# USBINFRTransiever_Microcontroller.net
KiCad netlist of a schematic drawn in Altium Designer
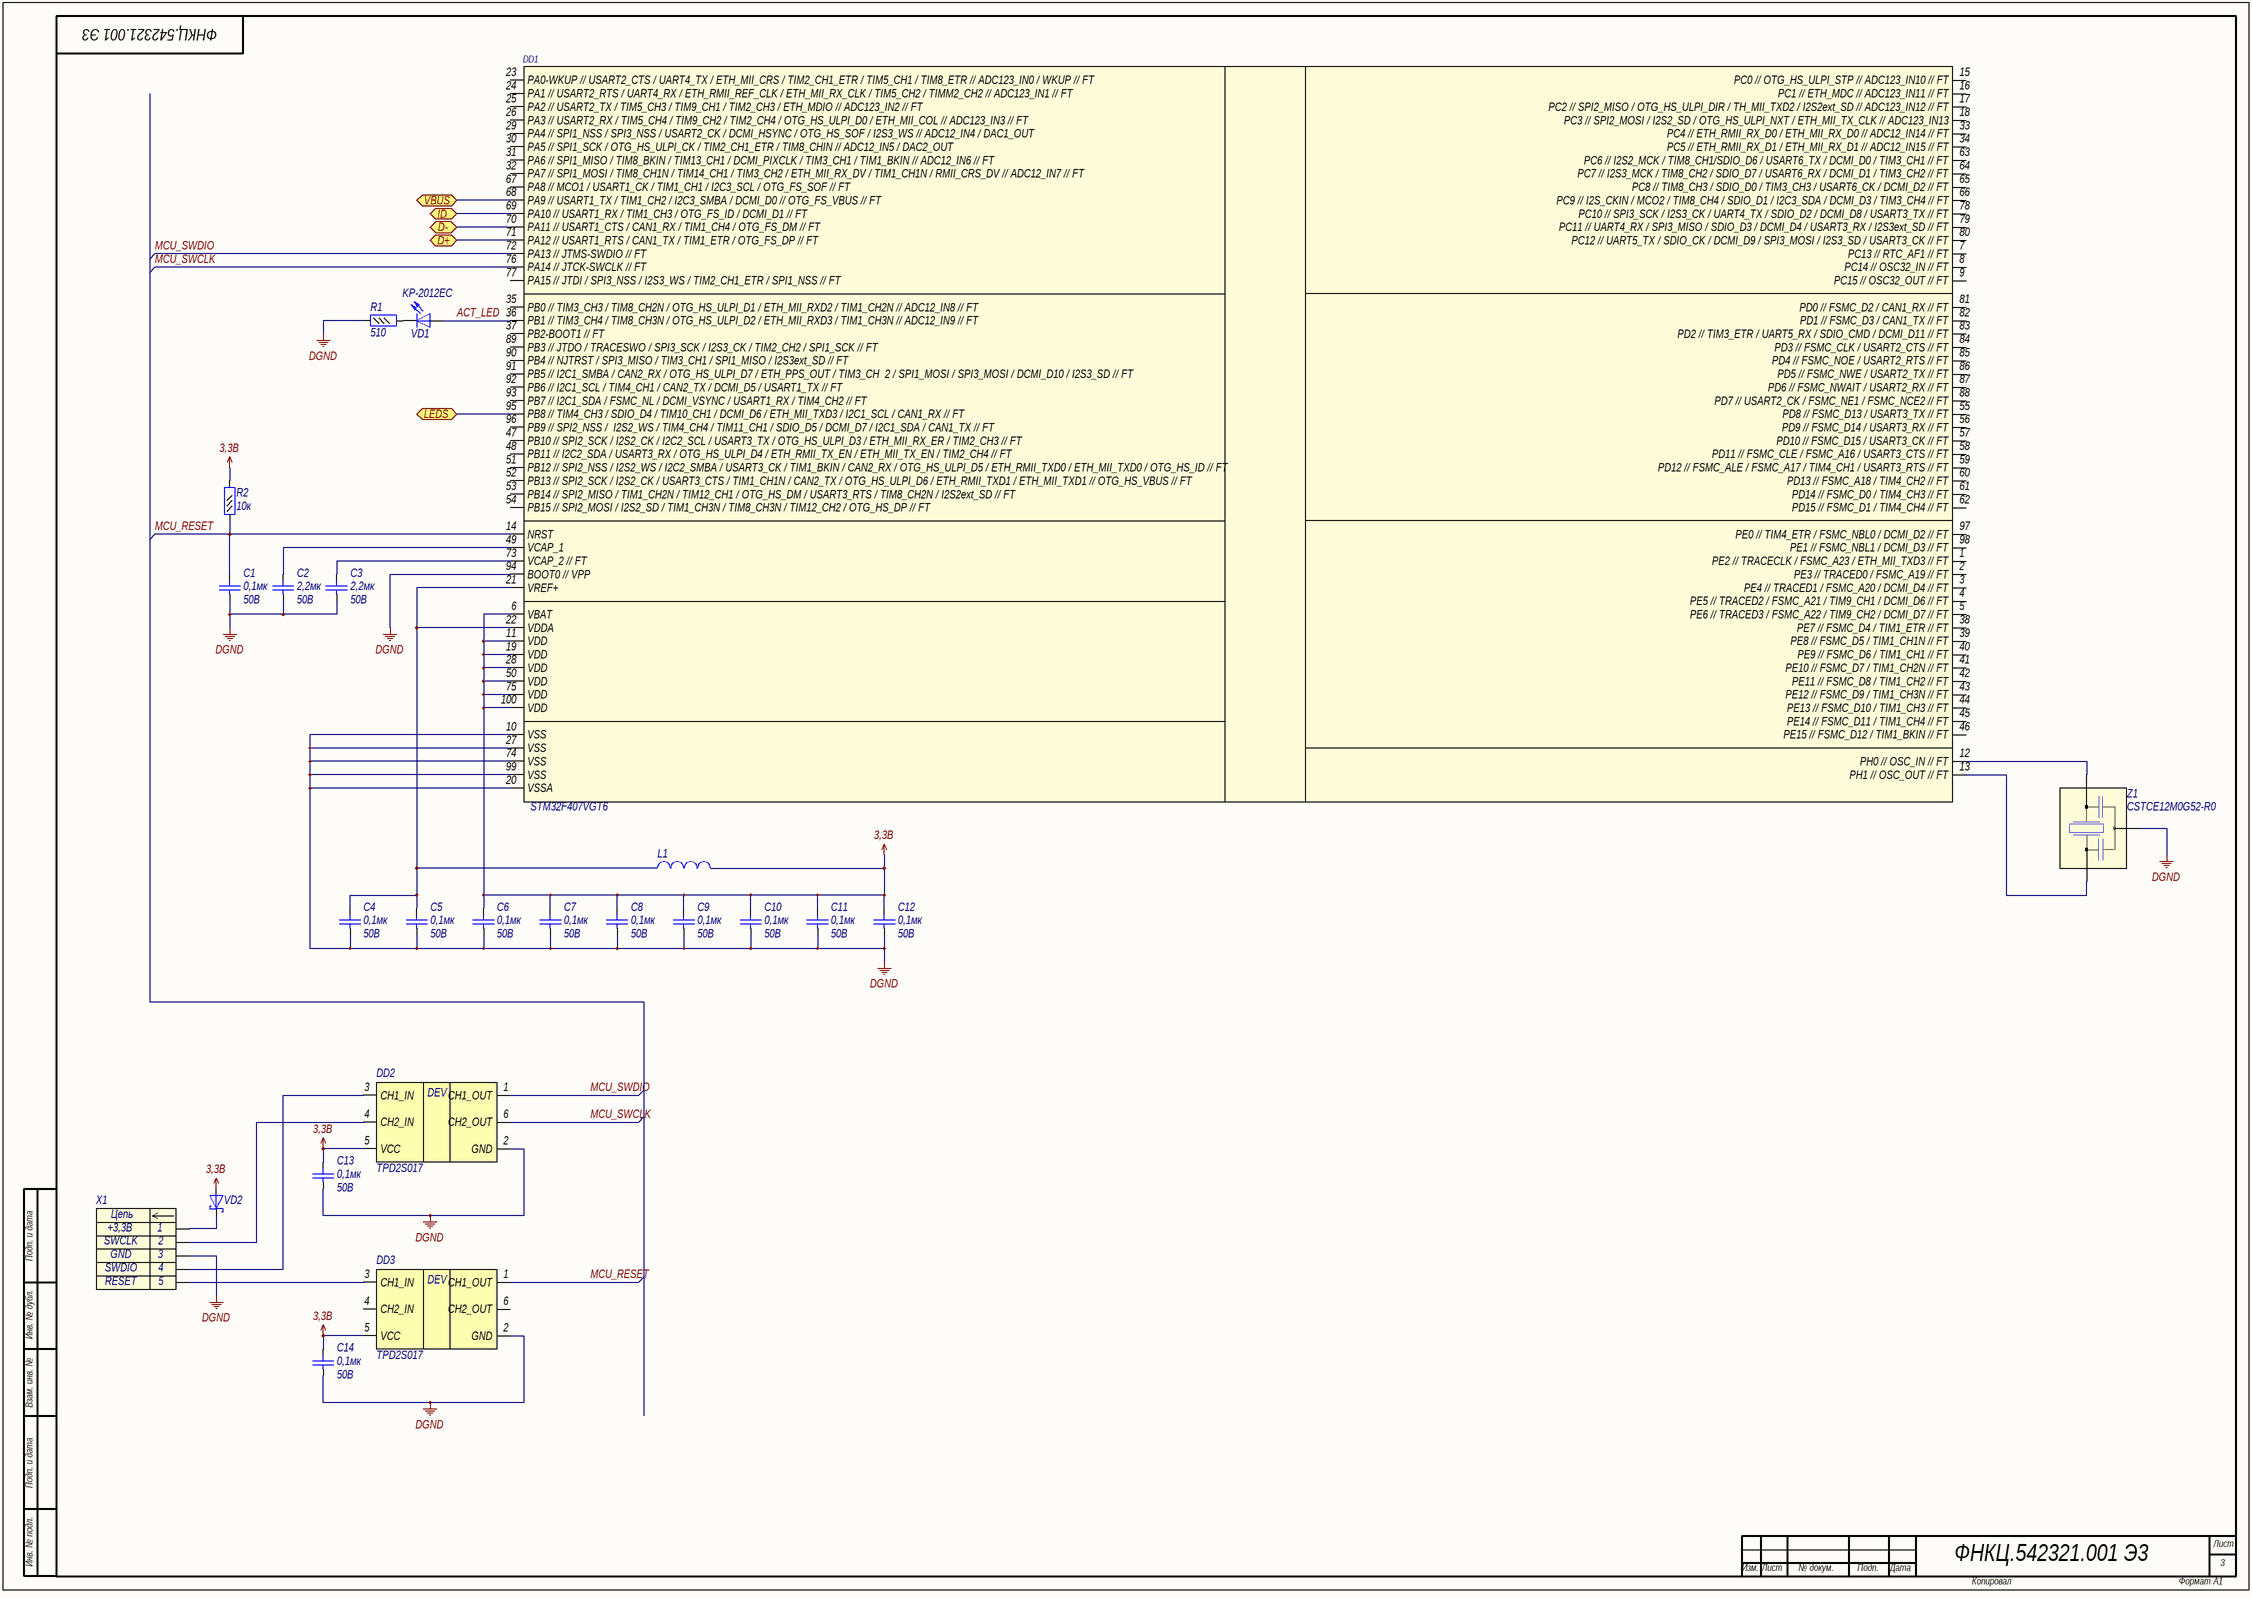
[diagram p0: USBINFRTransiever_Microcontroller.SchDoc]

(export (version "E")
  (design (tool "Eeschema 10.0.6"))
  (components
    (comp (ref "C1")
      (value "0,1мк")
      (footprint "C0603")
      (description "Конденсатор")
      (fields
        (field (name "VOLTAGE") "50B")
        (field (name "PART NUMBER") "GRM188R71H104K")
        (field (name "Comment") "Capacitor")
      )
      (libsource (lib "MOP44") (part "Capacitor"))
    )
    (comp (ref "C2")
      (value "2,2мк")
      (footprint "C0603")
      (description "Конденсатор")
      (fields
        (field (name "VOLTAGE") "50B")
        (field (name "PART NUMBER") "GRM188R71A225KE15D")
        (field (name "Comment") "Capacitor")
      )
      (libsource (lib "MOP44") (part "Capacitor"))
    )
    (comp (ref "C3")
      (value "2,2мк")
      (footprint "C0603")
      (description "Конденсатор")
      (fields
        (field (name "VOLTAGE") "50B")
        (field (name "PART NUMBER") "GRM188R71A225KE15D")
        (field (name "Comment") "Capacitor")
      )
      (libsource (lib "MOP44") (part "Capacitor"))
    )
    (comp (ref "C4")
      (value "0,1мк")
      (footprint "C0603")
      (description "Конденсатор")
      (fields
        (field (name "VOLTAGE") "50B")
        (field (name "PART NUMBER") "GRM188R71H104K")
        (field (name "Comment") "Capacitor")
      )
      (libsource (lib "MOP44") (part "Capacitor"))
    )
    (comp (ref "C5")
      (value "0,1мк")
      (footprint "C0603")
      (description "Конденсатор")
      (fields
        (field (name "VOLTAGE") "50B")
        (field (name "PART NUMBER") "GRM188R71H104K")
        (field (name "Comment") "Capacitor")
      )
      (libsource (lib "MOP44") (part "Capacitor"))
    )
    (comp (ref "C6")
      (value "0,1мк")
      (footprint "C0603")
      (description "Конденсатор")
      (fields
        (field (name "VOLTAGE") "50B")
        (field (name "PART NUMBER") "GRM188R71H104K")
        (field (name "Comment") "Capacitor")
      )
      (libsource (lib "MOP44") (part "Capacitor"))
    )
    (comp (ref "C7")
      (value "0,1мк")
      (footprint "C0603")
      (description "Конденсатор")
      (fields
        (field (name "VOLTAGE") "50B")
        (field (name "PART NUMBER") "GRM188R71H104K")
        (field (name "Comment") "Capacitor")
      )
      (libsource (lib "MOP44") (part "Capacitor"))
    )
    (comp (ref "C8")
      (value "0,1мк")
      (footprint "C0603")
      (description "Конденсатор")
      (fields
        (field (name "VOLTAGE") "50B")
        (field (name "PART NUMBER") "GRM188R71H104K")
        (field (name "Comment") "Capacitor")
      )
      (libsource (lib "MOP44") (part "Capacitor"))
    )
    (comp (ref "C9")
      (value "0,1мк")
      (footprint "C0603")
      (description "Конденсатор")
      (fields
        (field (name "VOLTAGE") "50B")
        (field (name "PART NUMBER") "GRM188R71H104K")
        (field (name "Comment") "Capacitor")
      )
      (libsource (lib "MOP44") (part "Capacitor"))
    )
    (comp (ref "C10")
      (value "0,1мк")
      (footprint "C0603")
      (description "Конденсатор")
      (fields
        (field (name "VOLTAGE") "50B")
        (field (name "PART NUMBER") "GRM188R71H104K")
        (field (name "Comment") "Capacitor")
      )
      (libsource (lib "MOP44") (part "Capacitor"))
    )
    (comp (ref "C11")
      (value "0,1мк")
      (footprint "C0603")
      (description "Конденсатор")
      (fields
        (field (name "VOLTAGE") "50B")
        (field (name "PART NUMBER") "GRM188R71H104K")
        (field (name "Comment") "Capacitor")
      )
      (libsource (lib "MOP44") (part "Capacitor"))
    )
    (comp (ref "C12")
      (value "0,1мк")
      (footprint "C0603")
      (description "Конденсатор")
      (fields
        (field (name "VOLTAGE") "50B")
        (field (name "PART NUMBER") "GRM188R71H104K")
        (field (name "Comment") "Capacitor")
      )
      (libsource (lib "MOP44") (part "Capacitor"))
    )
    (comp (ref "C13")
      (value "0,1мк")
      (footprint "C0603")
      (description "Конденсатор")
      (fields
        (field (name "VOLTAGE") "50B")
        (field (name "PART NUMBER") "GRM188R71H104K")
        (field (name "Comment") "Capacitor")
      )
      (libsource (lib "MOP44") (part "Capacitor"))
    )
    (comp (ref "C14")
      (value "0,1мк")
      (footprint "C0603")
      (description "Конденсатор")
      (fields
        (field (name "VOLTAGE") "50B")
        (field (name "PART NUMBER") "GRM188R71H104K")
        (field (name "Comment") "Capacitor")
      )
      (libsource (lib "MOP44") (part "Capacitor"))
    )
    (comp (ref "DD1")
      (value "STM32F407VGT6")
      (description "Микроконтроллер STM32F407VGT6")
      (libsource (lib "Microcontroller") (part "STM32F407VGT6"))
    )
    (comp (ref "DD2")
      (value "TPD2S017")
      (footprint "SOT23-6")
      (description "EMI Filter")
      (fields (field (name "PART NUMBER") "TPD2S017DBVR"))
      (libsource (lib "MOP44") (part "TPD2S017"))
    )
    (comp (ref "DD3")
      (value "TPD2S017")
      (footprint "SOT23-6")
      (description "EMI Filter")
      (fields (field (name "PART NUMBER") "TPD2S017DBVR"))
      (libsource (lib "MOP44") (part "TPD2S017"))
    )
    (comp (ref "L1")
      (value "Inductor")
      (footprint "L0603")
      (description "EMI Suppression Filter")
      (fields (field (name "PART NUMBER") "BLM18PG181SN1D"))
      (libsource (lib "MOP44") (part "Inductor"))
    )
    (comp (ref "R1")
      (value "510")
      (footprint "R0603")
      (description "Резистор")
      (fields (field (name "PART NUMBER") "RC0603FR-07510RL") (field (name "POWER") "0,062Вт"))
      (libsource (lib "MOP44") (part "Resistor_0,062Вт"))
    )
    (comp (ref "R2")
      (value "10к")
      (footprint "R0603")
      (description "Резистор")
      (fields (field (name "PART NUMBER") "RC0603FR-0710KL") (field (name "POWER") "0,062Вт"))
      (libsource (lib "") (part "Resistor_0,062Вт_1"))
    )
    (comp (ref "VD1")
      (value "LED")
      (footprint "L_0805")
      (description "Светодиод")
      (fields (field (name "PART NUMBER") "KP-2012EC"))
      (libsource (lib "MOP44") (part "LED"))
    )
    (comp (ref "VD2")
      (value "DiodeSchottky")
      (footprint "SOD-523")
      (description "Диод Шоттки")
      (fields (field (name "PART NUMBER") "PMEG2010AEB.115"))
      (libsource (lib "MOP44") (part "DiodeSchottky"))
    )
    (comp (ref "X1")
      (value "Header_5_plg")
      (footprint "PLS-5")
      (description "Разъем - 5 конт. вилка")
      (fields (field (name "PART NUMBER") "DS1021-1*5SF112-B"))
      (libsource (lib "MOP44") (part "Header_5_plg"))
    )
    (comp (ref "Z1")
      (value "QuartzWithCaps")
      (footprint "CSTCE")
      (description "Кварцевый резорнатор со встроенными нагрузочными конденсаторами")
      (fields (field (name "PART NUMBER") "CSTCE12M0G52-R0"))
      (libsource (lib "MOP44") (part "QuartzWithCaps"))
    )
  )
  (nets
    (net (code "1") (name "/ACT_LED") (class "Default")
      (node (ref "DD1") (pin "36") (pinfunction "PB1_//_TIM3_CH4_/_TIM8_CH3N_/_OTG_HS_ULPI_D2_/_ETH_MII_RXD3_/_TIM1_CH3N_//_ADC12_IN9_//_FT_36") (pintype "passive"))
      (node (ref "VD1") (pin "2") (pinfunction "A_2") (pintype "passive"))
    )
    (net (code "2") (name "/D+") (class "Default")
      (node (ref "DD1") (pin "71") (pinfunction "PA12_//_USART1_RTS_/_CAN1_TX_/_TIM1_ETR_/_OTG_FS_DP_//_FT_71") (pintype "passive"))
    )
    (net (code "3") (name "/D-") (class "Default")
      (node (ref "DD1") (pin "70") (pinfunction "PA11_//_USART1_CTS_/_CAN1_RX_/_TIM1_CH4_/_OTG_FS_DM_//_FT_70") (pintype "passive"))
    )
    (net (code "4") (name "/ID") (class "Default")
      (node (ref "DD1") (pin "69") (pinfunction "PA10_//_USART1_RX_/_TIM1_CH3_/_OTG_FS_ID_/_DCMI_D1_//_FT_69") (pintype "passive"))
    )
    (net (code "5") (name "/LEDS") (class "Default")
      (node (ref "DD1") (pin "95") (pinfunction "PB8_//_TIM4_CH3_/_SDIO_D4_/_TIM10_CH1_/_DCMI_D6_/_ETH_MII_TXD3_/_I2C1_SCL_/_CAN1_RX_//_FT_95") (pintype "passive"))
    )
    (net (code "6") (name "/MCU_RESET") (class "Default")
      (node (ref "C1") (pin "2") (pinfunction "2_2") (pintype "passive"))
      (node (ref "DD1") (pin "14") (pinfunction "NRST_14") (pintype "passive"))
      (node (ref "DD3") (pin "1") (pinfunction "CH1_OUT_1") (pintype "passive"))
      (node (ref "R2") (pin "1") (pinfunction "1_1") (pintype "passive"))
    )
    (net (code "7") (name "/MCU_SWCLK") (class "Default")
      (node (ref "DD1") (pin "76") (pinfunction "PA14_//_JTCK-SWCLK_//_FT_76") (pintype "passive"))
      (node (ref "DD2") (pin "6") (pinfunction "CH2_OUT_6") (pintype "passive"))
    )
    (net (code "8") (name "/MCU_SWDIO") (class "Default")
      (node (ref "DD1") (pin "72") (pinfunction "PA13_//_JTMS-SWDIO_//_FT_72") (pintype "passive"))
      (node (ref "DD2") (pin "1") (pinfunction "CH1_OUT_1") (pintype "passive"))
    )
    (net (code "9") (name "/VBUS") (class "Default")
      (node (ref "DD1") (pin "68") (pinfunction "PA9_//_USART1_TX_/_TIM1_CH2_/_I2C3_SMBA_/_DCMI_D0_//_OTG_FS_VBUS_//_FT_68") (pintype "passive"))
    )
    (net (code "10") (name "3,3B") (class "Default")
      (node (ref "C10") (pin "2") (pinfunction "2_2") (pintype "passive"))
      (node (ref "C11") (pin "2") (pinfunction "2_2") (pintype "passive"))
      (node (ref "C12") (pin "2") (pinfunction "2_2") (pintype "passive"))
      (node (ref "C13") (pin "2") (pinfunction "2_2") (pintype "passive"))
      (node (ref "C14") (pin "2") (pinfunction "2_2") (pintype "passive"))
      (node (ref "C6") (pin "2") (pinfunction "2_2") (pintype "passive"))
      (node (ref "C7") (pin "2") (pinfunction "2_2") (pintype "passive"))
      (node (ref "C8") (pin "2") (pinfunction "2_2") (pintype "passive"))
      (node (ref "C9") (pin "2") (pinfunction "2_2") (pintype "passive"))
      (node (ref "DD1") (pin "100") (pinfunction "VDD_100") (pintype "passive"))
      (node (ref "DD1") (pin "11") (pinfunction "VDD_11") (pintype "passive"))
      (node (ref "DD1") (pin "19") (pinfunction "VDD_19") (pintype "passive"))
      (node (ref "DD1") (pin "28") (pinfunction "VDD_28") (pintype "passive"))
      (node (ref "DD1") (pin "50") (pinfunction "VDD_50") (pintype "passive"))
      (node (ref "DD1") (pin "6") (pinfunction "VBAT_6") (pintype "passive"))
      (node (ref "DD1") (pin "75") (pinfunction "VDD_75") (pintype "passive"))
      (node (ref "DD2") (pin "5") (pinfunction "VCC_5") (pintype "power_in"))
      (node (ref "DD3") (pin "5") (pinfunction "VCC_5") (pintype "power_in"))
      (node (ref "L1") (pin "2") (pinfunction "2_2") (pintype "passive"))
      (node (ref "R2") (pin "2") (pinfunction "2_2") (pintype "passive"))
      (node (ref "VD2") (pin "2") (pinfunction "A_2") (pintype "passive"))
    )
    (net (code "11") (name "DGND") (class "Default")
      (node (ref "C1") (pin "1") (pinfunction "1_1") (pintype "passive"))
      (node (ref "C10") (pin "1") (pinfunction "1_1") (pintype "passive"))
      (node (ref "C11") (pin "1") (pinfunction "1_1") (pintype "passive"))
      (node (ref "C12") (pin "1") (pinfunction "1_1") (pintype "passive"))
      (node (ref "C13") (pin "1") (pinfunction "1_1") (pintype "passive"))
      (node (ref "C14") (pin "1") (pinfunction "1_1") (pintype "passive"))
      (node (ref "C2") (pin "1") (pinfunction "1_1") (pintype "passive"))
      (node (ref "C3") (pin "1") (pinfunction "1_1") (pintype "passive"))
      (node (ref "C4") (pin "1") (pinfunction "1_1") (pintype "passive"))
      (node (ref "C5") (pin "1") (pinfunction "1_1") (pintype "passive"))
      (node (ref "C6") (pin "1") (pinfunction "1_1") (pintype "passive"))
      (node (ref "C7") (pin "1") (pinfunction "1_1") (pintype "passive"))
      (node (ref "C8") (pin "1") (pinfunction "1_1") (pintype "passive"))
      (node (ref "C9") (pin "1") (pinfunction "1_1") (pintype "passive"))
      (node (ref "DD1") (pin "10") (pinfunction "VSS_10") (pintype "passive"))
      (node (ref "DD1") (pin "20") (pinfunction "VSSA_20") (pintype "passive"))
      (node (ref "DD1") (pin "27") (pinfunction "VSS_27") (pintype "passive"))
      (node (ref "DD1") (pin "74") (pinfunction "VSS_74") (pintype "passive"))
      (node (ref "DD1") (pin "94") (pinfunction "BOOT0_//_VPP_94") (pintype "passive"))
      (node (ref "DD1") (pin "99") (pinfunction "VSS_99") (pintype "passive"))
      (node (ref "DD2") (pin "2") (pinfunction "GND_2") (pintype "power_in"))
      (node (ref "DD3") (pin "2") (pinfunction "GND_2") (pintype "power_in"))
      (node (ref "R1") (pin "1") (pinfunction "1_1") (pintype "passive"))
      (node (ref "X1") (pin "3") (pinfunction "3_3") (pintype "passive"))
      (node (ref "Z1") (pin "2") (pinfunction "2_2") (pintype "passive"))
    )
    (net (code "12") (name "Net-(DD1-PH0_{slash}{slash}_OSC_IN_{slash}{slash}_FT)") (class "Default")
      (node (ref "DD1") (pin "12") (pinfunction "PH0_//_OSC_IN_//_FT_12") (pintype "passive"))
      (node (ref "Z1") (pin "3") (pinfunction "3_3") (pintype "passive"))
    )
    (net (code "13") (name "Net-(DD1-PH1_{slash}{slash}_OSC_OUT_{slash}{slash}_FT)") (class "Default")
      (node (ref "DD1") (pin "13") (pinfunction "PH1_//_OSC_OUT_//_FT_13") (pintype "passive"))
      (node (ref "Z1") (pin "1") (pinfunction "1_1") (pintype "passive"))
    )
    (net (code "14") (name "Net-(DD1-VCAP_1)") (class "Default")
      (node (ref "C2") (pin "2") (pinfunction "2_2") (pintype "passive"))
      (node (ref "DD1") (pin "49") (pinfunction "VCAP_1_49") (pintype "passive"))
    )
    (net (code "15") (name "Net-(DD1-VCAP_2_{slash}{slash}_FT)") (class "Default")
      (node (ref "C3") (pin "2") (pinfunction "2_2") (pintype "passive"))
      (node (ref "DD1") (pin "73") (pinfunction "VCAP_2_//_FT_73") (pintype "passive"))
    )
    (net (code "16") (name "Net-(DD1-VDDA)") (class "Default")
      (node (ref "C4") (pin "2") (pinfunction "2_2") (pintype "passive"))
      (node (ref "C5") (pin "2") (pinfunction "2_2") (pintype "passive"))
      (node (ref "DD1") (pin "21") (pinfunction "VREF+_21") (pintype "passive"))
      (node (ref "DD1") (pin "22") (pinfunction "VDDA_22") (pintype "passive"))
      (node (ref "L1") (pin "1") (pinfunction "1_1") (pintype "passive"))
    )
    (net (code "17") (name "Net-(DD2-CH1_IN)") (class "Default")
      (node (ref "DD2") (pin "3") (pinfunction "CH1_IN_3") (pintype "passive"))
      (node (ref "X1") (pin "4") (pinfunction "4_4") (pintype "passive"))
    )
    (net (code "18") (name "Net-(DD2-CH2_IN)") (class "Default")
      (node (ref "DD2") (pin "4") (pinfunction "CH2_IN_4") (pintype "passive"))
      (node (ref "X1") (pin "2") (pinfunction "2_2") (pintype "passive"))
    )
    (net (code "19") (name "Net-(DD3-CH1_IN)") (class "Default")
      (node (ref "DD3") (pin "3") (pinfunction "CH1_IN_3") (pintype "passive"))
      (node (ref "X1") (pin "5") (pinfunction "5_5") (pintype "passive"))
    )
    (net (code "20") (name "Net-(VD1-K)") (class "Default")
      (node (ref "R1") (pin "2") (pinfunction "2_2") (pintype "passive"))
      (node (ref "VD1") (pin "1") (pinfunction "K_1") (pintype "passive"))
    )
    (net (code "21") (name "Net-(VD2-K)") (class "Default")
      (node (ref "VD2") (pin "1") (pinfunction "K_1") (pintype "passive"))
      (node (ref "X1") (pin "1") (pinfunction "1_1") (pintype "passive"))
    )
    (net (code "22") (name "unconnected-(DD1-PA0-WKUP_{slash}{slash}_USART2_CTS_{slash}_UART4_TX_{slash}_ETH_MII_CRS_{slash}_TIM2_CH1_ETR_{slash}_TIM5_CH1_{slash}_TIM8_ETR_{slash}{slash}_ADC123_IN0_{slash}_WKUP_{slash}{slash}_FT-Pad23)") (class "Default")
      (node (ref "DD1") (pin "23") (pinfunction "PA0-WKUP_//_USART2_CTS_/_UART4_TX_/_ETH_MII_CRS_/_TIM2_CH1_ETR_/_TIM5_CH1_/_TIM8_ETR_//_ADC123_IN0_/_WKUP_//_FT_23") (pintype "passive"))
    )
    (net (code "23") (name "unconnected-(DD1-PA1_{slash}{slash}_USART2_RTS_{slash}_UART4_RX_{slash}_ETH_RMII_REF_CLK_{slash}_ETH_MII_RX_CLK_{slash}_TIM5_CH2_{slash}_TIMM2_CH2_{slash}{slash}_ADC123_IN1_{slash}{slash}_FT-Pad24)") (class "Default")
      (node (ref "DD1") (pin "24") (pinfunction "PA1_//_USART2_RTS_/_UART4_RX_/_ETH_RMII_REF_CLK_/_ETH_MII_RX_CLK_/_TIM5_CH2_/_TIMM2_CH2_//_ADC123_IN1_//_FT_24") (pintype "passive"))
    )
    (net (code "24") (name "unconnected-(DD1-PA2_{slash}{slash}_USART2_TX_{slash}_TIM5_CH3_{slash}_TIM9_CH1_{slash}_TIM2_CH3_{slash}_ETH_MDIO_{slash}{slash}_ADC123_IN2_{slash}{slash}_FT-Pad25)") (class "Default")
      (node (ref "DD1") (pin "25") (pinfunction "PA2_//_USART2_TX_/_TIM5_CH3_/_TIM9_CH1_/_TIM2_CH3_/_ETH_MDIO_//_ADC123_IN2_//_FT_25") (pintype "passive"))
    )
    (net (code "25") (name "unconnected-(DD1-PA3_{slash}{slash}_USART2_RX_{slash}_TIM5_CH4_{slash}_TIM9_CH2_{slash}_TIM2_CH4_{slash}_OTG_HS_ULPI_D0_{slash}_ETH_MII_COL_{slash}{slash}_ADC123_IN3_{slash}{slash}_FT-Pad26)") (class "Default")
      (node (ref "DD1") (pin "26") (pinfunction "PA3_//_USART2_RX_/_TIM5_CH4_/_TIM9_CH2_/_TIM2_CH4_/_OTG_HS_ULPI_D0_/_ETH_MII_COL_//_ADC123_IN3_//_FT_26") (pintype "passive"))
    )
    (net (code "26") (name "unconnected-(DD1-PA4_{slash}{slash}_SPI1_NSS_{slash}_SPI3_NSS_{slash}_USART2_CK_{slash}_DCMI_HSYNC_{slash}_OTG_HS_SOF_{slash}_I2S3_WS_{slash}{slash}_ADC12_IN4_{slash}_DAC1_OUT-Pad29)") (class "Default")
      (node (ref "DD1") (pin "29") (pinfunction "PA4_//_SPI1_NSS_/_SPI3_NSS_/_USART2_CK_/_DCMI_HSYNC_/_OTG_HS_SOF_/_I2S3_WS_//_ADC12_IN4_/_DAC1_OUT_29") (pintype "passive"))
    )
    (net (code "27") (name "unconnected-(DD1-PA5_{slash}{slash}_SPI1_SCK_{slash}_OTG_HS_ULPI_CK_{slash}_TIM2_CH1_ETR_{slash}_TIM8_CHIN_{slash}{slash}_ADC12_IN5_{slash}_DAC2_OUT-Pad30)") (class "Default")
      (node (ref "DD1") (pin "30") (pinfunction "PA5_//_SPI1_SCK_/_OTG_HS_ULPI_CK_/_TIM2_CH1_ETR_/_TIM8_CHIN_//_ADC12_IN5_/_DAC2_OUT_30") (pintype "passive"))
    )
    (net (code "28") (name "unconnected-(DD1-PA6_{slash}{slash}_SPI1_MISO_{slash}_TIM8_BKIN_{slash}_TIM13_CH1_{slash}_DCMI_PIXCLK_{slash}_TIM3_CH1_{slash}_TIM1_BKIN_{slash}{slash}_ADC12_IN6_{slash}{slash}_FT-Pad31)") (class "Default")
      (node (ref "DD1") (pin "31") (pinfunction "PA6_//_SPI1_MISO_/_TIM8_BKIN_/_TIM13_CH1_/_DCMI_PIXCLK_/_TIM3_CH1_/_TIM1_BKIN_//_ADC12_IN6_//_FT_31") (pintype "passive"))
    )
    (net (code "29") (name "unconnected-(DD1-PA7_{slash}{slash}_SPI1_MOSI_{slash}_TIM8_CH1N_{slash}_TIM14_CH1_{slash}_TIM3_CH2_{slash}_ETH_MII_RX_DV_{slash}_TIM1_CH1N_{slash}_RMII_CRS_DV_{slash}{slash}_ADC12_IN7_{slash}{slash}_FT-Pad32)") (class "Default")
      (node (ref "DD1") (pin "32") (pinfunction "PA7_//_SPI1_MOSI_/_TIM8_CH1N_/_TIM14_CH1_/_TIM3_CH2_/_ETH_MII_RX_DV_/_TIM1_CH1N_/_RMII_CRS_DV_//_ADC12_IN7_//_FT_32") (pintype "passive"))
    )
    (net (code "30") (name "unconnected-(DD1-PA8_{slash}{slash}_MCO1_{slash}_USART1_CK_{slash}_TIM1_CH1_{slash}_I2C3_SCL_{slash}_OTG_FS_SOF_{slash}{slash}_FT-Pad67)") (class "Default")
      (node (ref "DD1") (pin "67") (pinfunction "PA8_//_MCO1_/_USART1_CK_/_TIM1_CH1_/_I2C3_SCL_/_OTG_FS_SOF_//_FT_67") (pintype "passive"))
    )
    (net (code "31") (name "unconnected-(DD1-PA15_{slash}{slash}_JTDI_{slash}_SPI3_NSS_{slash}_I2S3_WS_{slash}_TIM2_CH1_ETR_{slash}_SPI1_NSS_{slash}{slash}_FT-Pad77)") (class "Default")
      (node (ref "DD1") (pin "77") (pinfunction "PA15_//_JTDI_/_SPI3_NSS_/_I2S3_WS_/_TIM2_CH1_ETR_/_SPI1_NSS_//_FT_77") (pintype "passive"))
    )
    (net (code "32") (name "unconnected-(DD1-PB0_{slash}{slash}_TIM3_CH3_{slash}_TIM8_CH2N_{slash}_OTG_HS_ULPI_D1_{slash}_ETH_MII_RXD2_{slash}_TIM1_CH2N_{slash}{slash}_ADC12_IN8_{slash}{slash}_FT-Pad35)") (class "Default")
      (node (ref "DD1") (pin "35") (pinfunction "PB0_//_TIM3_CH3_/_TIM8_CH2N_/_OTG_HS_ULPI_D1_/_ETH_MII_RXD2_/_TIM1_CH2N_//_ADC12_IN8_//_FT_35") (pintype "passive"))
    )
    (net (code "33") (name "unconnected-(DD1-PB2-BOOT1_{slash}{slash}_FT-Pad37)") (class "Default")
      (node (ref "DD1") (pin "37") (pinfunction "PB2-BOOT1_//_FT_37") (pintype "passive"))
    )
    (net (code "34") (name "unconnected-(DD1-PB3_{slash}{slash}_JTDO_{slash}_TRACESWO_{slash}_SPI3_SCK_{slash}_I2S3_CK_{slash}_TIM2_CH2_{slash}_SPI1_SCK_{slash}{slash}_FT-Pad89)") (class "Default")
      (node (ref "DD1") (pin "89") (pinfunction "PB3_//_JTDO_/_TRACESWO_/_SPI3_SCK_/_I2S3_CK_/_TIM2_CH2_/_SPI1_SCK_//_FT_89") (pintype "passive"))
    )
    (net (code "35") (name "unconnected-(DD1-PB4_{slash}{slash}_NJTRST_{slash}_SPI3_MISO_{slash}_TIM3_CH1_{slash}_SPI1_MISO_{slash}_I2S3ext_SD_{slash}{slash}_FT-Pad90)") (class "Default")
      (node (ref "DD1") (pin "90") (pinfunction "PB4_//_NJTRST_/_SPI3_MISO_/_TIM3_CH1_/_SPI1_MISO_/_I2S3ext_SD_//_FT_90") (pintype "passive"))
    )
    (net (code "36") (name "unconnected-(DD1-PB5_{slash}{slash}_I2C1_SMBA_{slash}_CAN2_RX_{slash}_OTG_HS_ULPI_D7_{slash}_ETH_PPS_OUT_{slash}_TIM3_CH__2_{slash}_SPI1_MOSI_{slash}_SPI3_MOSI_{slash}_DCMI_D10_{slash}_I2S3_SD_{slash}{slash}_FT-Pad91)") (class "Default")
      (node (ref "DD1") (pin "91") (pinfunction "PB5_//_I2C1_SMBA_/_CAN2_RX_/_OTG_HS_ULPI_D7_/_ETH_PPS_OUT_/_TIM3_CH__2_/_SPI1_MOSI_/_SPI3_MOSI_/_DCMI_D10_/_I2S3_SD_//_FT_91") (pintype "passive"))
    )
    (net (code "37") (name "unconnected-(DD1-PB6_{slash}{slash}_I2C1_SCL_{slash}_TIM4_CH1_{slash}_CAN2_TX_{slash}_DCMI_D5_{slash}_USART1_TX_{slash}{slash}_FT-Pad92)") (class "Default")
      (node (ref "DD1") (pin "92") (pinfunction "PB6_//_I2C1_SCL_/_TIM4_CH1_/_CAN2_TX_/_DCMI_D5_/_USART1_TX_//_FT_92") (pintype "passive"))
    )
    (net (code "38") (name "unconnected-(DD1-PB7_{slash}{slash}_I2C1_SDA_{slash}_FSMC_NL_{slash}_DCMI_VSYNC_{slash}_USART1_RX_{slash}_TIM4_CH2_{slash}{slash}_FT-Pad93)") (class "Default")
      (node (ref "DD1") (pin "93") (pinfunction "PB7_//_I2C1_SDA_/_FSMC_NL_/_DCMI_VSYNC_/_USART1_RX_/_TIM4_CH2_//_FT_93") (pintype "passive"))
    )
    (net (code "39") (name "unconnected-(DD1-PB9_{slash}{slash}_SPI2_NSS_{slash}__I2S2_WS_{slash}_TIM4_CH4_{slash}_TIM11_CH1_{slash}_SDIO_D5_{slash}_DCMI_D7_{slash}_I2C1_SDA_{slash}_CAN1_TX_{slash}{slash}_FT-Pad96)") (class "Default")
      (node (ref "DD1") (pin "96") (pinfunction "PB9_//_SPI2_NSS_/__I2S2_WS_/_TIM4_CH4_/_TIM11_CH1_/_SDIO_D5_/_DCMI_D7_/_I2C1_SDA_/_CAN1_TX_//_FT_96") (pintype "passive"))
    )
    (net (code "40") (name "unconnected-(DD1-PB10_{slash}{slash}_SPI2_SCK_{slash}_I2S2_CK_{slash}_I2C2_SCL_{slash}_USART3_TX_{slash}_OTG_HS_ULPI_D3_{slash}_ETH_MII_RX_ER_{slash}_TIM2_CH3_{slash}{slash}_FT-Pad47)") (class "Default")
      (node (ref "DD1") (pin "47") (pinfunction "PB10_//_SPI2_SCK_/_I2S2_CK_/_I2C2_SCL_/_USART3_TX_/_OTG_HS_ULPI_D3_/_ETH_MII_RX_ER_/_TIM2_CH3_//_FT_47") (pintype "passive"))
    )
    (net (code "41") (name "unconnected-(DD1-PB11_{slash}{slash}_I2C2_SDA_{slash}_USART3_RX_{slash}_OTG_HS_ULPI_D4_{slash}_ETH_RMII_TX_EN_{slash}_ETH_MII_TX_EN_{slash}_TIM2_CH4_{slash}{slash}_FT-Pad48)") (class "Default")
      (node (ref "DD1") (pin "48") (pinfunction "PB11_//_I2C2_SDA_/_USART3_RX_/_OTG_HS_ULPI_D4_/_ETH_RMII_TX_EN_/_ETH_MII_TX_EN_/_TIM2_CH4_//_FT_48") (pintype "passive"))
    )
    (net (code "42") (name "unconnected-(DD1-PB12_{slash}{slash}_SPI2_NSS_{slash}_I2S2_WS_{slash}_I2C2_SMBA_{slash}_USART3_CK_{slash}_TIM1_BKIN_{slash}_CAN2_RX_{slash}_OTG_HS_ULPI_D5_{slash}_ETH_RMII_TXD0_{slash}_ETH_MII_TXD0_{slash}_OTG_HS_ID_{slash}{slash}_FT-Pad51)") (class "Default")
      (node (ref "DD1") (pin "51") (pinfunction "PB12_//_SPI2_NSS_/_I2S2_WS_/_I2C2_SMBA_/_USART3_CK_/_TIM1_BKIN_/_CAN2_RX_/_OTG_HS_ULPI_D5_/_ETH_RMII_TXD0_/_ETH_MII_TXD0_/_OTG_HS_ID_//_FT_51") (pintype "passive"))
    )
    (net (code "43") (name "unconnected-(DD1-PB13_{slash}{slash}_SPI2_SCK_{slash}_I2S2_CK_{slash}_USART3_CTS_{slash}_TIM1_CH1N_{slash}_CAN2_TX_{slash}_OTG_HS_ULPI_D6_{slash}_ETH_RMII_TXD1_{slash}_ETH_MII_TXD1_{slash}{slash}_OTG_HS_VBUS_{slash}{slash}_FT-Pad52)") (class "Default")
      (node (ref "DD1") (pin "52") (pinfunction "PB13_//_SPI2_SCK_/_I2S2_CK_/_USART3_CTS_/_TIM1_CH1N_/_CAN2_TX_/_OTG_HS_ULPI_D6_/_ETH_RMII_TXD1_/_ETH_MII_TXD1_//_OTG_HS_VBUS_//_FT_52") (pintype "passive"))
    )
    (net (code "44") (name "unconnected-(DD1-PB14_{slash}{slash}_SPI2_MISO_{slash}_TIM1_CH2N_{slash}_TIM12_CH1_{slash}_OTG_HS_DM_{slash}_USART3_RTS_{slash}_TIM8_CH2N_{slash}_I2S2ext_SD_{slash}{slash}_FT-Pad53)") (class "Default")
      (node (ref "DD1") (pin "53") (pinfunction "PB14_//_SPI2_MISO_/_TIM1_CH2N_/_TIM12_CH1_/_OTG_HS_DM_/_USART3_RTS_/_TIM8_CH2N_/_I2S2ext_SD_//_FT_53") (pintype "passive"))
    )
    (net (code "45") (name "unconnected-(DD1-PB15_{slash}{slash}_SPI2_MOSI_{slash}_I2S2_SD_{slash}_TIM1_CH3N_{slash}_TIM8_CH3N_{slash}_TIM12_CH2_{slash}_OTG_HS_DP_{slash}{slash}_FT-Pad54)") (class "Default")
      (node (ref "DD1") (pin "54") (pinfunction "PB15_//_SPI2_MOSI_/_I2S2_SD_/_TIM1_CH3N_/_TIM8_CH3N_/_TIM12_CH2_/_OTG_HS_DP_//_FT_54") (pintype "passive"))
    )
    (net (code "46") (name "unconnected-(DD1-PC0_{slash}{slash}_OTG_HS_ULPI_STP_{slash}{slash}_ADC123_IN10_{slash}{slash}_FT-Pad15)") (class "Default")
      (node (ref "DD1") (pin "15") (pinfunction "PC0_//_OTG_HS_ULPI_STP_//_ADC123_IN10_//_FT_15") (pintype "passive"))
    )
    (net (code "47") (name "unconnected-(DD1-PC1_{slash}{slash}_ETH_MDC_{slash}{slash}_ADC123_IN11_{slash}{slash}_FT-Pad16)") (class "Default")
      (node (ref "DD1") (pin "16") (pinfunction "PC1_//_ETH_MDC_//_ADC123_IN11_//_FT_16") (pintype "passive"))
    )
    (net (code "48") (name "unconnected-(DD1-PC2_{slash}{slash}_SPI2_MISO_{slash}_OTG_HS_ULPI_DIR_{slash}_TH_MII_TXD2_{slash}_I2S2ext_SD_{slash}{slash}_ADC123_IN12_{slash}{slash}_FT-Pad17)") (class "Default")
      (node (ref "DD1") (pin "17") (pinfunction "PC2_//_SPI2_MISO_/_OTG_HS_ULPI_DIR_/_TH_MII_TXD2_/_I2S2ext_SD_//_ADC123_IN12_//_FT_17") (pintype "passive"))
    )
    (net (code "49") (name "unconnected-(DD1-PC3_{slash}{slash}_SPI2_MOSI_{slash}_I2S2_SD_{slash}_OTG_HS_ULPI_NXT_{slash}_ETH_MII_TX_CLK_{slash}{slash}_ADC123_IN13-Pad18)") (class "Default")
      (node (ref "DD1") (pin "18") (pinfunction "PC3_//_SPI2_MOSI_/_I2S2_SD_/_OTG_HS_ULPI_NXT_/_ETH_MII_TX_CLK_//_ADC123_IN13_18") (pintype "passive"))
    )
    (net (code "50") (name "unconnected-(DD1-PC4_{slash}{slash}_ETH_RMII_RX_D0_{slash}_ETH_MII_RX_D0_{slash}{slash}_ADC12_IN14_{slash}{slash}_FT-Pad33)") (class "Default")
      (node (ref "DD1") (pin "33") (pinfunction "PC4_//_ETH_RMII_RX_D0_/_ETH_MII_RX_D0_//_ADC12_IN14_//_FT_33") (pintype "passive"))
    )
    (net (code "51") (name "unconnected-(DD1-PC5_{slash}{slash}_ETH_RMII_RX_D1_{slash}_ETH_MII_RX_D1_{slash}{slash}_ADC12_IN15_{slash}{slash}_FT-Pad34)") (class "Default")
      (node (ref "DD1") (pin "34") (pinfunction "PC5_//_ETH_RMII_RX_D1_/_ETH_MII_RX_D1_//_ADC12_IN15_//_FT_34") (pintype "passive"))
    )
    (net (code "52") (name "unconnected-(DD1-PC6_{slash}{slash}_I2S2_MCK_{slash}_TIM8_CH1{slash}SDIO_D6_{slash}_USART6_TX_{slash}_DCMI_D0_{slash}_TIM3_CH1_{slash}{slash}_FT-Pad63)") (class "Default")
      (node (ref "DD1") (pin "63") (pinfunction "PC6_//_I2S2_MCK_/_TIM8_CH1/SDIO_D6_/_USART6_TX_/_DCMI_D0_/_TIM3_CH1_//_FT_63") (pintype "passive"))
    )
    (net (code "53") (name "unconnected-(DD1-PC7_{slash}{slash}_I2S3_MCK_{slash}_TIM8_CH2_{slash}_SDIO_D7_{slash}_USART6_RX_{slash}_DCMI_D1_{slash}_TIM3_CH2_{slash}{slash}_FT-Pad64)") (class "Default")
      (node (ref "DD1") (pin "64") (pinfunction "PC7_//_I2S3_MCK_/_TIM8_CH2_/_SDIO_D7_/_USART6_RX_/_DCMI_D1_/_TIM3_CH2_//_FT_64") (pintype "passive"))
    )
    (net (code "54") (name "unconnected-(DD1-PC8_{slash}{slash}_TIM8_CH3_{slash}_SDIO_D0_{slash}_TIM3_CH3_{slash}_USART6_CK_{slash}_DCMI_D2_{slash}{slash}_FT-Pad65)") (class "Default")
      (node (ref "DD1") (pin "65") (pinfunction "PC8_//_TIM8_CH3_/_SDIO_D0_/_TIM3_CH3_/_USART6_CK_/_DCMI_D2_//_FT_65") (pintype "passive"))
    )
    (net (code "55") (name "unconnected-(DD1-PC9_{slash}{slash}_I2S_CKIN_{slash}_MCO2_{slash}_TIM8_CH4_{slash}_SDIO_D1_{slash}_I2C3_SDA_{slash}_DCMI_D3_{slash}_TIM3_CH4_{slash}{slash}_FT-Pad66)") (class "Default")
      (node (ref "DD1") (pin "66") (pinfunction "PC9_//_I2S_CKIN_/_MCO2_/_TIM8_CH4_/_SDIO_D1_/_I2C3_SDA_/_DCMI_D3_/_TIM3_CH4_//_FT_66") (pintype "passive"))
    )
    (net (code "56") (name "unconnected-(DD1-PC10_{slash}{slash}_SPI3_SCK_{slash}_I2S3_CK_{slash}_UART4_TX_{slash}_SDIO_D2_{slash}_DCMI_D8_{slash}_USART3_TX_{slash}{slash}_FT-Pad78)") (class "Default")
      (node (ref "DD1") (pin "78") (pinfunction "PC10_//_SPI3_SCK_/_I2S3_CK_/_UART4_TX_/_SDIO_D2_/_DCMI_D8_/_USART3_TX_//_FT_78") (pintype "passive"))
    )
    (net (code "57") (name "unconnected-(DD1-PC11_{slash}{slash}_UART4_RX_{slash}_SPI3_MISO_{slash}_SDIO_D3_{slash}_DCMI_D4_{slash}_USART3_RX_{slash}_I2S3ext_SD_{slash}{slash}_FT-Pad79)") (class "Default")
      (node (ref "DD1") (pin "79") (pinfunction "PC11_//_UART4_RX_/_SPI3_MISO_/_SDIO_D3_/_DCMI_D4_/_USART3_RX_/_I2S3ext_SD_//_FT_79") (pintype "passive"))
    )
    (net (code "58") (name "unconnected-(DD1-PC12_{slash}{slash}_UART5_TX_{slash}_SDIO_CK_{slash}_DCMI_D9_{slash}_SPI3_MOSI_{slash}_I2S3_SD_{slash}_USART3_CK_{slash}{slash}_FT-Pad80)") (class "Default")
      (node (ref "DD1") (pin "80") (pinfunction "PC12_//_UART5_TX_/_SDIO_CK_/_DCMI_D9_/_SPI3_MOSI_/_I2S3_SD_/_USART3_CK_//_FT_80") (pintype "passive"))
    )
    (net (code "59") (name "unconnected-(DD1-PC13_{slash}{slash}_RTC_AF1_{slash}{slash}_FT-Pad7)") (class "Default")
      (node (ref "DD1") (pin "7") (pinfunction "PC13_//_RTC_AF1_//_FT_7") (pintype "passive"))
    )
    (net (code "60") (name "unconnected-(DD1-PC14_{slash}{slash}_OSC32_IN_{slash}{slash}_FT-Pad8)") (class "Default")
      (node (ref "DD1") (pin "8") (pinfunction "PC14_//_OSC32_IN_//_FT_8") (pintype "passive"))
    )
    (net (code "61") (name "unconnected-(DD1-PC15_{slash}{slash}_OSC32_OUT_{slash}{slash}_FT-Pad9)") (class "Default")
      (node (ref "DD1") (pin "9") (pinfunction "PC15_//_OSC32_OUT_//_FT_9") (pintype "passive"))
    )
    (net (code "62") (name "unconnected-(DD1-PD0_{slash}{slash}_FSMC_D2_{slash}_CAN1_RX_{slash}{slash}_FT-Pad81)") (class "Default")
      (node (ref "DD1") (pin "81") (pinfunction "PD0_//_FSMC_D2_/_CAN1_RX_//_FT_81") (pintype "passive"))
    )
    (net (code "63") (name "unconnected-(DD1-PD1_{slash}{slash}_FSMC_D3_{slash}_CAN1_TX_{slash}{slash}_FT-Pad82)") (class "Default")
      (node (ref "DD1") (pin "82") (pinfunction "PD1_//_FSMC_D3_/_CAN1_TX_//_FT_82") (pintype "passive"))
    )
    (net (code "64") (name "unconnected-(DD1-PD2_{slash}{slash}_TIM3_ETR_{slash}_UART5_RX_{slash}_SDIO_CMD_{slash}_DCMI_D11_{slash}{slash}_FT-Pad83)") (class "Default")
      (node (ref "DD1") (pin "83") (pinfunction "PD2_//_TIM3_ETR_/_UART5_RX_/_SDIO_CMD_/_DCMI_D11_//_FT_83") (pintype "passive"))
    )
    (net (code "65") (name "unconnected-(DD1-PD3_{slash}{slash}_FSMC_CLK_{slash}_USART2_CTS_{slash}{slash}_FT-Pad84)") (class "Default")
      (node (ref "DD1") (pin "84") (pinfunction "PD3_//_FSMC_CLK_/_USART2_CTS_//_FT_84") (pintype "passive"))
    )
    (net (code "66") (name "unconnected-(DD1-PD4_{slash}{slash}_FSMC_NOE_{slash}_USART2_RTS_{slash}{slash}_FT-Pad85)") (class "Default")
      (node (ref "DD1") (pin "85") (pinfunction "PD4_//_FSMC_NOE_/_USART2_RTS_//_FT_85") (pintype "passive"))
    )
    (net (code "67") (name "unconnected-(DD1-PD5_{slash}{slash}_FSMC_NWE_{slash}_USART2_TX_{slash}{slash}_FT-Pad86)") (class "Default")
      (node (ref "DD1") (pin "86") (pinfunction "PD5_//_FSMC_NWE_/_USART2_TX_//_FT_86") (pintype "passive"))
    )
    (net (code "68") (name "unconnected-(DD1-PD6_{slash}{slash}_FSMC_NWAIT_{slash}_USART2_RX_{slash}{slash}_FT-Pad87)") (class "Default")
      (node (ref "DD1") (pin "87") (pinfunction "PD6_//_FSMC_NWAIT_/_USART2_RX_//_FT_87") (pintype "passive"))
    )
    (net (code "69") (name "unconnected-(DD1-PD7_{slash}{slash}_USART2_CK_{slash}_FSMC_NE1_{slash}_FSMC_NCE2_{slash}{slash}_FT-Pad88)") (class "Default")
      (node (ref "DD1") (pin "88") (pinfunction "PD7_//_USART2_CK_/_FSMC_NE1_/_FSMC_NCE2_//_FT_88") (pintype "passive"))
    )
    (net (code "70") (name "unconnected-(DD1-PD8_{slash}{slash}_FSMC_D13_{slash}_USART3_TX_{slash}{slash}_FT-Pad55)") (class "Default")
      (node (ref "DD1") (pin "55") (pinfunction "PD8_//_FSMC_D13_/_USART3_TX_//_FT_55") (pintype "passive"))
    )
    (net (code "71") (name "unconnected-(DD1-PD9_{slash}{slash}_FSMC_D14_{slash}_USART3_RX_{slash}{slash}_FT-Pad56)") (class "Default")
      (node (ref "DD1") (pin "56") (pinfunction "PD9_//_FSMC_D14_/_USART3_RX_//_FT_56") (pintype "passive"))
    )
    (net (code "72") (name "unconnected-(DD1-PD10_{slash}{slash}_FSMC_D15_{slash}_USART3_CK_{slash}{slash}_FT-Pad57)") (class "Default")
      (node (ref "DD1") (pin "57") (pinfunction "PD10_//_FSMC_D15_/_USART3_CK_//_FT_57") (pintype "passive"))
    )
    (net (code "73") (name "unconnected-(DD1-PD11_{slash}{slash}_FSMC_CLE_{slash}_FSMC_A16_{slash}_USART3_CTS_{slash}{slash}_FT-Pad58)") (class "Default")
      (node (ref "DD1") (pin "58") (pinfunction "PD11_//_FSMC_CLE_/_FSMC_A16_/_USART3_CTS_//_FT_58") (pintype "passive"))
    )
    (net (code "74") (name "unconnected-(DD1-PD12_{slash}{slash}_FSMC_ALE_{slash}_FSMC_A17_{slash}_TIM4_CH1_{slash}_USART3_RTS_{slash}{slash}_FT-Pad59)") (class "Default")
      (node (ref "DD1") (pin "59") (pinfunction "PD12_//_FSMC_ALE_/_FSMC_A17_/_TIM4_CH1_/_USART3_RTS_//_FT_59") (pintype "passive"))
    )
    (net (code "75") (name "unconnected-(DD1-PD13_{slash}{slash}_FSMC_A18_{slash}_TIM4_CH2_{slash}{slash}_FT-Pad60)") (class "Default")
      (node (ref "DD1") (pin "60") (pinfunction "PD13_//_FSMC_A18_/_TIM4_CH2_//_FT_60") (pintype "passive"))
    )
    (net (code "76") (name "unconnected-(DD1-PD14_{slash}{slash}_FSMC_D0_{slash}_TIM4_CH3_{slash}{slash}_FT-Pad61)") (class "Default")
      (node (ref "DD1") (pin "61") (pinfunction "PD14_//_FSMC_D0_/_TIM4_CH3_//_FT_61") (pintype "passive"))
    )
    (net (code "77") (name "unconnected-(DD1-PD15_{slash}{slash}_FSMC_D1_{slash}_TIM4_CH4_{slash}{slash}_FT-Pad62)") (class "Default")
      (node (ref "DD1") (pin "62") (pinfunction "PD15_//_FSMC_D1_/_TIM4_CH4_//_FT_62") (pintype "passive"))
    )
    (net (code "78") (name "unconnected-(DD1-PE0_{slash}{slash}_TIM4_ETR_{slash}_FSMC_NBL0_{slash}_DCMI_D2_{slash}{slash}_FT-Pad97)") (class "Default")
      (node (ref "DD1") (pin "97") (pinfunction "PE0_//_TIM4_ETR_/_FSMC_NBL0_/_DCMI_D2_//_FT_97") (pintype "passive"))
    )
    (net (code "79") (name "unconnected-(DD1-PE1_{slash}{slash}_FSMC_NBL1_{slash}_DCMI_D3_{slash}{slash}_FT-Pad98)") (class "Default")
      (node (ref "DD1") (pin "98") (pinfunction "PE1_//_FSMC_NBL1_/_DCMI_D3_//_FT_98") (pintype "passive"))
    )
    (net (code "80") (name "unconnected-(DD1-PE2_{slash}{slash}_TRACECLK_{slash}_FSMC_A23_{slash}_ETH_MII_TXD3_{slash}{slash}_FT-Pad1)") (class "Default")
      (node (ref "DD1") (pin "1") (pinfunction "PE2_//_TRACECLK_/_FSMC_A23_/_ETH_MII_TXD3_//_FT_1") (pintype "passive"))
    )
    (net (code "81") (name "unconnected-(DD1-PE3_{slash}{slash}_TRACED0_{slash}_FSMC_A19_{slash}{slash}_FT-Pad2)") (class "Default")
      (node (ref "DD1") (pin "2") (pinfunction "PE3_//_TRACED0_/_FSMC_A19_//_FT_2") (pintype "passive"))
    )
    (net (code "82") (name "unconnected-(DD1-PE4_{slash}{slash}_TRACED1_{slash}_FSMC_A20_{slash}_DCMI_D4_{slash}{slash}_FT-Pad3)") (class "Default")
      (node (ref "DD1") (pin "3") (pinfunction "PE4_//_TRACED1_/_FSMC_A20_/_DCMI_D4_//_FT_3") (pintype "passive"))
    )
    (net (code "83") (name "unconnected-(DD1-PE5_{slash}{slash}_TRACED2_{slash}_FSMC_A21_{slash}_TIM9_CH1_{slash}_DCMI_D6_{slash}{slash}_FT-Pad4)") (class "Default")
      (node (ref "DD1") (pin "4") (pinfunction "PE5_//_TRACED2_/_FSMC_A21_/_TIM9_CH1_/_DCMI_D6_//_FT_4") (pintype "passive"))
    )
    (net (code "84") (name "unconnected-(DD1-PE6_{slash}{slash}_TRACED3_{slash}_FSMC_A22_{slash}_TIM9_CH2_{slash}_DCMI_D7_{slash}{slash}_FT-Pad5)") (class "Default")
      (node (ref "DD1") (pin "5") (pinfunction "PE6_//_TRACED3_/_FSMC_A22_/_TIM9_CH2_/_DCMI_D7_//_FT_5") (pintype "passive"))
    )
    (net (code "85") (name "unconnected-(DD1-PE7_{slash}{slash}_FSMC_D4_{slash}_TIM1_ETR_{slash}{slash}_FT-Pad38)") (class "Default")
      (node (ref "DD1") (pin "38") (pinfunction "PE7_//_FSMC_D4_/_TIM1_ETR_//_FT_38") (pintype "passive"))
    )
    (net (code "86") (name "unconnected-(DD1-PE8_{slash}{slash}_FSMC_D5_{slash}_TIM1_CH1N_{slash}{slash}_FT-Pad39)") (class "Default")
      (node (ref "DD1") (pin "39") (pinfunction "PE8_//_FSMC_D5_/_TIM1_CH1N_//_FT_39") (pintype "passive"))
    )
    (net (code "87") (name "unconnected-(DD1-PE9_{slash}{slash}_FSMC_D6_{slash}_TIM1_CH1_{slash}{slash}_FT-Pad40)") (class "Default")
      (node (ref "DD1") (pin "40") (pinfunction "PE9_//_FSMC_D6_/_TIM1_CH1_//_FT_40") (pintype "passive"))
    )
    (net (code "88") (name "unconnected-(DD1-PE10_{slash}{slash}_FSMC_D7_{slash}_TIM1_CH2N_{slash}{slash}_FT-Pad41)") (class "Default")
      (node (ref "DD1") (pin "41") (pinfunction "PE10_//_FSMC_D7_/_TIM1_CH2N_//_FT_41") (pintype "passive"))
    )
    (net (code "89") (name "unconnected-(DD1-PE11_{slash}{slash}_FSMC_D8_{slash}_TIM1_CH2_{slash}{slash}_FT-Pad42)") (class "Default")
      (node (ref "DD1") (pin "42") (pinfunction "PE11_//_FSMC_D8_/_TIM1_CH2_//_FT_42") (pintype "passive"))
    )
    (net (code "90") (name "unconnected-(DD1-PE12_{slash}{slash}_FSMC_D9_{slash}_TIM1_CH3N_{slash}{slash}_FT-Pad43)") (class "Default")
      (node (ref "DD1") (pin "43") (pinfunction "PE12_//_FSMC_D9_/_TIM1_CH3N_//_FT_43") (pintype "passive"))
    )
    (net (code "91") (name "unconnected-(DD1-PE13_{slash}{slash}_FSMC_D10_{slash}_TIM1_CH3_{slash}{slash}_FT-Pad44)") (class "Default")
      (node (ref "DD1") (pin "44") (pinfunction "PE13_//_FSMC_D10_/_TIM1_CH3_//_FT_44") (pintype "passive"))
    )
    (net (code "92") (name "unconnected-(DD1-PE14_{slash}{slash}_FSMC_D11_{slash}_TIM1_CH4_{slash}{slash}_FT-Pad45)") (class "Default")
      (node (ref "DD1") (pin "45") (pinfunction "PE14_//_FSMC_D11_/_TIM1_CH4_//_FT_45") (pintype "passive"))
    )
    (net (code "93") (name "unconnected-(DD1-PE15_{slash}{slash}_FSMC_D12_{slash}_TIM1_BKIN_{slash}{slash}_FT-Pad46)") (class "Default")
      (node (ref "DD1") (pin "46") (pinfunction "PE15_//_FSMC_D12_/_TIM1_BKIN_//_FT_46") (pintype "passive"))
    )
    (net (code "94") (name "unconnected-(DD3-CH2_IN-Pad4)") (class "Default")
      (node (ref "DD3") (pin "4") (pinfunction "CH2_IN_4") (pintype "passive"))
    )
    (net (code "95") (name "unconnected-(DD3-CH2_OUT-Pad6)") (class "Default")
      (node (ref "DD3") (pin "6") (pinfunction "CH2_OUT_6") (pintype "passive"))
    )
  )
)
